# turbiditySensor.net
KiCad netlist of a schematic drawn in EAGLE
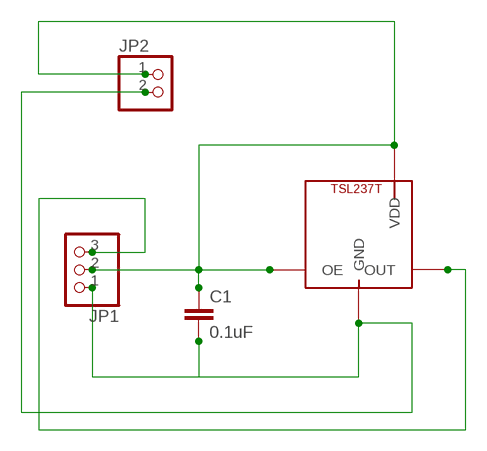
[diagram p0: schematic, sheet 1]

(export (version "E")
  (design (tool "Eeschema 10.0.6"))
  (components
    (comp (ref "C1")
      (value "0.1uF")
      (footprint "eagle-import:0603")
      (libsource (lib "eagle-import") (part "0.1UF-0603-25V-5%"))
    )
    (comp (ref "JP1")
      (value "PINHD-1X3")
      (footprint "eagle-import:1X03")
      (libsource (lib "eagle-import") (part "PINHD-1X3"))
    )
    (comp (ref "JP2")
      (value "PINHD-1X2")
      (footprint "eagle-import:1X02")
      (libsource (lib "eagle-import") (part "PINHD-1X2"))
    )
    (comp (ref "SENSOR")
      (value "WS2812B3535")
      (footprint "eagle-import:LED3535")
      (libsource (lib "eagle-import") (part "WS2812B3535"))
    )
  )
  (nets
    (net (code "1") (name "Net-(SENSOR-GND)") (class "Default")
      (node (ref "C1") (pin "2") (pinfunction "2_2") (pintype "passive"))
      (node (ref "JP1") (pin "1") (pinfunction "1_1") (pintype "passive"))
      (node (ref "JP2") (pin "2") (pinfunction "2_2") (pintype "passive"))
      (node (ref "SENSOR") (pin "2") (pinfunction "GND_2") (pintype "power_in"))
    )
    (net (code "2") (name "Net-(SENSOR-OE)") (class "Default")
      (node (ref "C1") (pin "1") (pinfunction "1_1") (pintype "passive"))
      (node (ref "JP1") (pin "2") (pinfunction "2_2") (pintype "passive"))
      (node (ref "JP2") (pin "1") (pinfunction "1_1") (pintype "passive"))
      (node (ref "SENSOR") (pin "1") (pinfunction "OE_1") (pintype "input"))
      (node (ref "SENSOR") (pin "3") (pinfunction "VDD_3") (pintype "power_in"))
    )
    (net (code "3") (name "Net-(SENSOR-OUT)") (class "Default")
      (node (ref "JP1") (pin "3") (pinfunction "3_3") (pintype "passive"))
      (node (ref "SENSOR") (pin "4") (pinfunction "OUT_4") (pintype "output"))
    )
  )
)
